# Sch_front_led.net
KiCad netlist of a schematic drawn in Altium Designer
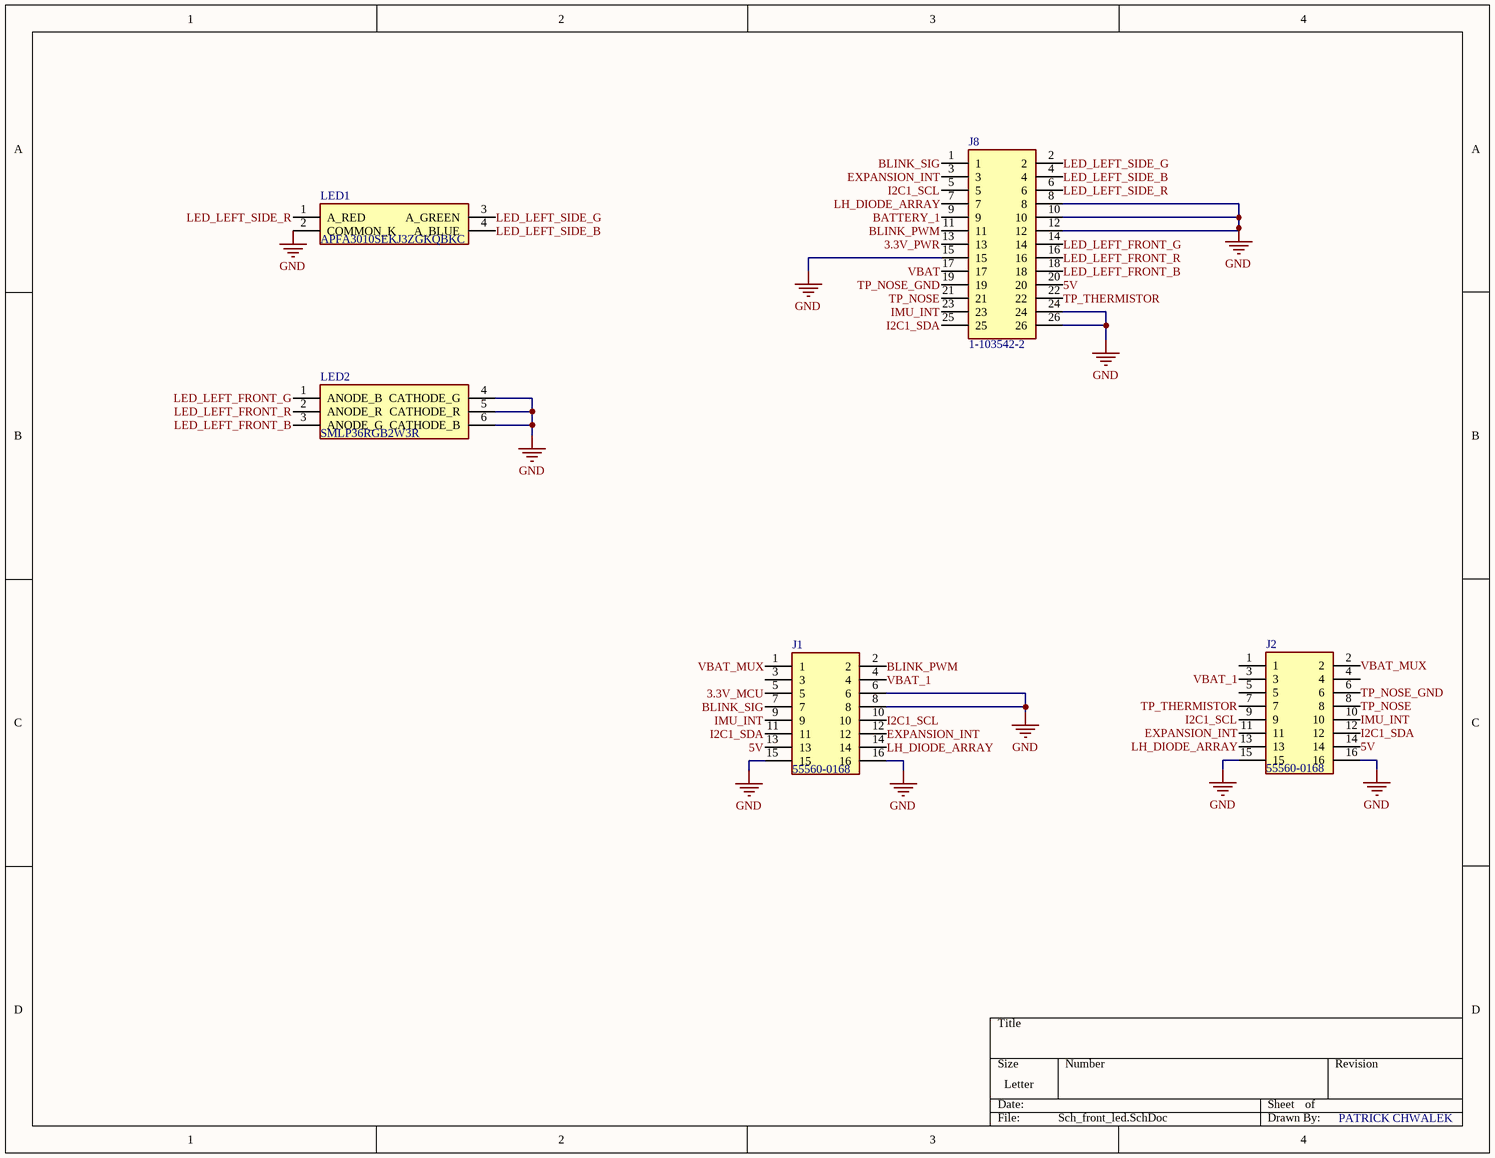
[diagram p0: Sch_front_led.SchDoc]

(export (version "E")
  (design (tool "Eeschema 10.0.6"))
  (components
    (comp (ref "J1")
      (value "55560-0168")
      (footprint "SamacSys:555600168")
      (description "Connector")
      (fields (field (name "MOUSER PART NUMBER") "538-55560-0168") (field (name "RS PART NUMBER") "7206558P"))
      (libsource (lib "*") (part "55560-0168"))
    )
    (comp (ref "J2")
      (value "55560-0168")
      (footprint "SamacSys:555600168")
      (description "Connector")
      (fields (field (name "MOUSER PART NUMBER") "538-55560-0168") (field (name "RS PART NUMBER") "7206558P"))
      (libsource (lib "*") (part "55560-0168"))
    )
    (comp (ref "J8")
      (value "1-103542-2")
      (footprint "SamacSys:HDRV26W89P254X254_2X13_3261X506X1074P")
      (description "Connector")
      (fields (field (name "MOUSER PART NUMBER") "571-1-103542-2"))
      (libsource (lib "*") (part "1-103542-2"))
    )
    (comp (ref "LED1")
      (value "APFA3010SEKJ3ZGKQBKC")
      (footprint "SamacSys:KPFA-3010RGBC-11")
      (description "LED")
      (fields (field (name "MOUSER PART NUMBER") "604-APFA3010SEKJ3ZGK"))
      (libsource (lib "*") (part "APFA3010SEKJ3ZGKQBKC"))
    )
    (comp (ref "LED2")
      (value "SMLP36RGB2W3R")
      (footprint "ROHM-1510-(0604)")
      (description "LED")
      (fields
        (field (name "MOUSER PART NUMBER") "755-SMLP36RGB2W3R")
        (field (name "RS PART NUMBER") "1246884")
      )
      (libsource (lib "*") (part "SMLP36RGB2W3R"))
    )
  )
  (nets
    (net (code "1") (name "/3.3V_MCU") (class "Default")
      (node (ref "J1") (pin "5") (pinfunction "5_5") (pintype "passive"))
    )
    (net (code "2") (name "/3.3V_PWR") (class "Default")
      (node (ref "J8") (pin "13") (pinfunction "13_13") (pintype "passive"))
    )
    (net (code "3") (name "/5V") (class "Default")
      (node (ref "J1") (pin "13") (pinfunction "13_13") (pintype "passive"))
      (node (ref "J2") (pin "14") (pinfunction "14_14") (pintype "passive"))
      (node (ref "J8") (pin "20") (pinfunction "20_20") (pintype "passive"))
    )
    (net (code "4") (name "/BATTERY_1") (class "Default")
      (node (ref "J8") (pin "9") (pinfunction "9_9") (pintype "passive"))
    )
    (net (code "5") (name "/BLINK_PWM") (class "Default")
      (node (ref "J1") (pin "2") (pinfunction "2_2") (pintype "passive"))
      (node (ref "J8") (pin "11") (pinfunction "11_11") (pintype "passive"))
    )
    (net (code "6") (name "/BLINK_SIG") (class "Default")
      (node (ref "J1") (pin "7") (pinfunction "7_7") (pintype "passive"))
      (node (ref "J8") (pin "1") (pinfunction "1_1") (pintype "passive"))
    )
    (net (code "7") (name "/EXPANSION_INT") (class "Default")
      (node (ref "J1") (pin "12") (pinfunction "12_12") (pintype "passive"))
      (node (ref "J2") (pin "11") (pinfunction "11_11") (pintype "passive"))
      (node (ref "J8") (pin "3") (pinfunction "3_3") (pintype "passive"))
    )
    (net (code "8") (name "/I2C1_SCL") (class "Default")
      (node (ref "J1") (pin "10") (pinfunction "10_10") (pintype "passive"))
      (node (ref "J2") (pin "9") (pinfunction "9_9") (pintype "passive"))
      (node (ref "J8") (pin "5") (pinfunction "5_5") (pintype "passive"))
    )
    (net (code "9") (name "/I2C1_SDA") (class "Default")
      (node (ref "J1") (pin "11") (pinfunction "11_11") (pintype "passive"))
      (node (ref "J2") (pin "12") (pinfunction "12_12") (pintype "passive"))
      (node (ref "J8") (pin "25") (pinfunction "25_25") (pintype "passive"))
    )
    (net (code "10") (name "/IMU_INT") (class "Default")
      (node (ref "J1") (pin "9") (pinfunction "9_9") (pintype "passive"))
      (node (ref "J2") (pin "10") (pinfunction "10_10") (pintype "passive"))
      (node (ref "J8") (pin "23") (pinfunction "23_23") (pintype "passive"))
    )
    (net (code "11") (name "/LED_LEFT_FRONT_B") (class "Default")
      (node (ref "J8") (pin "18") (pinfunction "18_18") (pintype "passive"))
      (node (ref "LED2") (pin "3") (pinfunction "ANODE_G_3") (pintype "passive"))
    )
    (net (code "12") (name "/LED_LEFT_FRONT_G") (class "Default")
      (node (ref "J8") (pin "14") (pinfunction "14_14") (pintype "passive"))
      (node (ref "LED2") (pin "1") (pinfunction "ANODE_B_1") (pintype "passive"))
    )
    (net (code "13") (name "/LED_LEFT_FRONT_R") (class "Default")
      (node (ref "J8") (pin "16") (pinfunction "16_16") (pintype "passive"))
      (node (ref "LED2") (pin "2") (pinfunction "ANODE_R_2") (pintype "passive"))
    )
    (net (code "14") (name "/LED_LEFT_SIDE_B") (class "Default")
      (node (ref "J8") (pin "4") (pinfunction "4_4") (pintype "passive"))
      (node (ref "LED1") (pin "4") (pinfunction "A_BLUE_4") (pintype "passive"))
    )
    (net (code "15") (name "/LED_LEFT_SIDE_G") (class "Default")
      (node (ref "J8") (pin "2") (pinfunction "2_2") (pintype "passive"))
      (node (ref "LED1") (pin "3") (pinfunction "A_GREEN_3") (pintype "passive"))
    )
    (net (code "16") (name "/LED_LEFT_SIDE_R") (class "Default")
      (node (ref "J8") (pin "6") (pinfunction "6_6") (pintype "passive"))
      (node (ref "LED1") (pin "1") (pinfunction "A_RED_1") (pintype "passive"))
    )
    (net (code "17") (name "/LH_DIODE_ARRAY") (class "Default")
      (node (ref "J1") (pin "14") (pinfunction "14_14") (pintype "passive"))
      (node (ref "J2") (pin "13") (pinfunction "13_13") (pintype "passive"))
      (node (ref "J8") (pin "7") (pinfunction "7_7") (pintype "passive"))
    )
    (net (code "18") (name "/TP_NOSE") (class "Default")
      (node (ref "J2") (pin "8") (pinfunction "8_8") (pintype "passive"))
      (node (ref "J8") (pin "21") (pinfunction "21_21") (pintype "passive"))
    )
    (net (code "19") (name "/TP_NOSE_GND") (class "Default")
      (node (ref "J2") (pin "6") (pinfunction "6_6") (pintype "passive"))
      (node (ref "J8") (pin "19") (pinfunction "19_19") (pintype "passive"))
    )
    (net (code "20") (name "/TP_THERMISTOR") (class "Default")
      (node (ref "J2") (pin "7") (pinfunction "7_7") (pintype "passive"))
      (node (ref "J8") (pin "22") (pinfunction "22_22") (pintype "passive"))
    )
    (net (code "21") (name "/VBAT") (class "Default")
      (node (ref "J8") (pin "17") (pinfunction "17_17") (pintype "passive"))
    )
    (net (code "22") (name "/VBAT_1") (class "Default")
      (node (ref "J1") (pin "4") (pinfunction "4_4") (pintype "passive"))
      (node (ref "J2") (pin "3") (pinfunction "3_3") (pintype "passive"))
    )
    (net (code "23") (name "/VBAT_MUX") (class "Default")
      (node (ref "J1") (pin "1") (pinfunction "1_1") (pintype "passive"))
      (node (ref "J2") (pin "2") (pinfunction "2_2") (pintype "passive"))
    )
    (net (code "24") (name "GND") (class "Default")
      (node (ref "J1") (pin "15") (pinfunction "15_15") (pintype "passive"))
      (node (ref "J1") (pin "16") (pinfunction "16_16") (pintype "passive"))
      (node (ref "J1") (pin "6") (pinfunction "6_6") (pintype "passive"))
      (node (ref "J1") (pin "8") (pinfunction "8_8") (pintype "passive"))
      (node (ref "J2") (pin "15") (pinfunction "15_15") (pintype "passive"))
      (node (ref "J2") (pin "16") (pinfunction "16_16") (pintype "passive"))
      (node (ref "J8") (pin "10") (pinfunction "10_10") (pintype "passive"))
      (node (ref "J8") (pin "12") (pinfunction "12_12") (pintype "passive"))
      (node (ref "J8") (pin "15") (pinfunction "15_15") (pintype "passive"))
      (node (ref "J8") (pin "24") (pinfunction "24_24") (pintype "passive"))
      (node (ref "J8") (pin "26") (pinfunction "26_26") (pintype "passive"))
      (node (ref "J8") (pin "8") (pinfunction "8_8") (pintype "passive"))
      (node (ref "LED1") (pin "2") (pinfunction "COMMON_K_2") (pintype "passive"))
      (node (ref "LED2") (pin "4") (pinfunction "CATHODE_G_4") (pintype "passive"))
      (node (ref "LED2") (pin "5") (pinfunction "CATHODE_R_5") (pintype "passive"))
      (node (ref "LED2") (pin "6") (pinfunction "CATHODE_B_6") (pintype "passive"))
    )
    (net (code "25") (name "unconnected-(J1-Pad3)") (class "Default")
      (node (ref "J1") (pin "3") (pinfunction "3_3") (pintype "passive"))
    )
    (net (code "26") (name "unconnected-(J2-Pad1)") (class "Default")
      (node (ref "J2") (pin "1") (pinfunction "1_1") (pintype "passive"))
    )
    (net (code "27") (name "unconnected-(J2-Pad4)") (class "Default")
      (node (ref "J2") (pin "4") (pinfunction "4_4") (pintype "passive"))
    )
    (net (code "28") (name "unconnected-(J2-Pad5)") (class "Default")
      (node (ref "J2") (pin "5") (pinfunction "5_5") (pintype "passive"))
    )
  )
)
